# CON_RS232DCE_DB9.net
KiCad netlist of a schematic drawn in Altium Designer
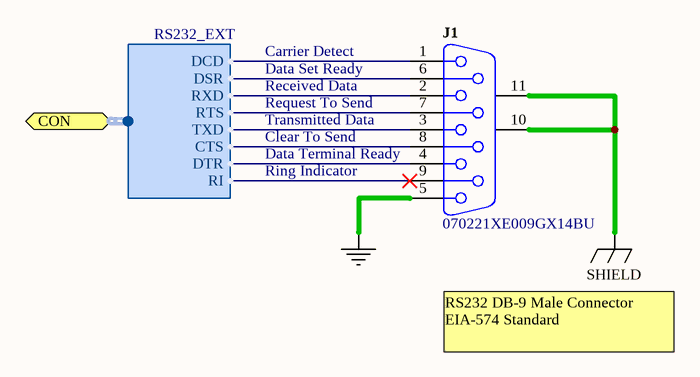
[diagram p0: CON_RS232DCE_DB9.SchDoc]

(export (version "E")
  (design (tool "Eeschema 10.0.6"))
  (components
    (comp (ref "J1")
      (value "070221XE009GX14BU")
      (footprint "070221XE009GX14BU")
      (description "Connector DB9 SMD Male/Pins; SUYIN")
      (libsource (lib "AltiumDesignLibrary") (part "CON-DB-9-M-RA"))
    )
  )
  (nets
    (net (code "2") (name "/CTS") (class "Default")
      (node (ref "J1") (pin "8") (pinfunction "8_8") (pintype "passive"))
    )
    (net (code "3") (name "/DCD") (class "Default")
      (node (ref "J1") (pin "1") (pinfunction "1_1") (pintype "passive"))
    )
    (net (code "4") (name "/DSR") (class "Default")
      (node (ref "J1") (pin "6") (pinfunction "6_6") (pintype "passive"))
    )
    (net (code "5") (name "/DTR") (class "Default")
      (node (ref "J1") (pin "4") (pinfunction "4_4") (pintype "passive"))
    )
    (net (code "6") (name "/RI") (class "Default")
      (node (ref "J1") (pin "9") (pinfunction "9_9") (pintype "passive+no_connect"))
    )
    (net (code "7") (name "/RTS") (class "Default")
      (node (ref "J1") (pin "7") (pinfunction "7_7") (pintype "passive"))
    )
    (net (code "8") (name "/RXD") (class "Default")
      (node (ref "J1") (pin "2") (pinfunction "2_2") (pintype "passive"))
    )
    (net (code "9") (name "/TXD") (class "Default")
      (node (ref "J1") (pin "3") (pinfunction "3_3") (pintype "passive"))
    )
    (net (code "11") (name "GND") (class "Default")
      (node (ref "J1") (pin "5") (pinfunction "5_5") (pintype "passive"))
    )
    (net (code "12") (name "SHIELD") (class "Default")
      (node (ref "J1") (pin "10") (pinfunction "MH1_10") (pintype "passive"))
      (node (ref "J1") (pin "11") (pinfunction "MH2_11") (pintype "passive"))
    )
  )
)
